# eeZeePowerJack.net
KiCad netlist of a schematic drawn in EAGLE
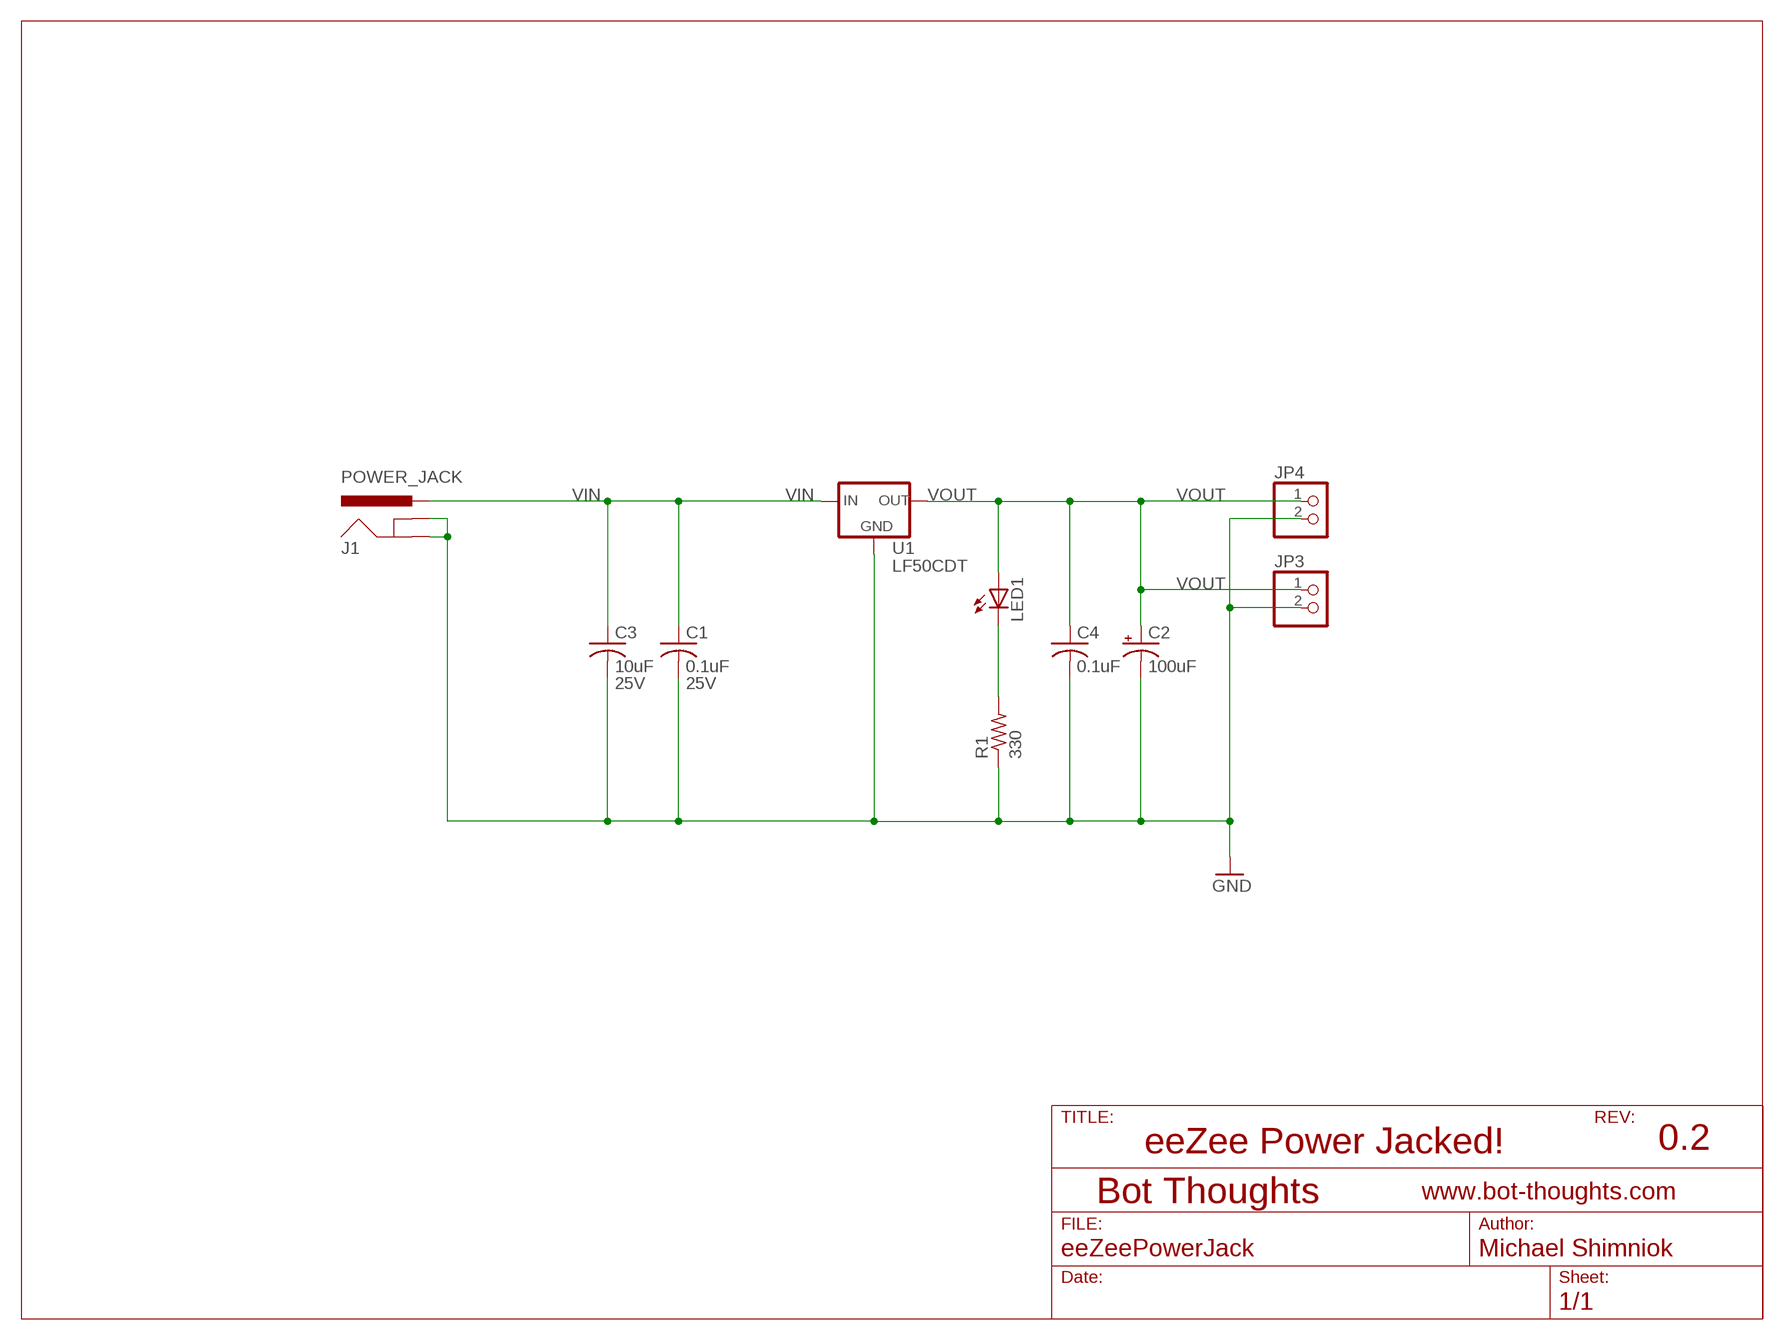
[diagram p0: schematic, sheet 1]

(export (version "E")
  (design (tool "Eeschema 10.0.6"))
  (components
    (comp (ref "C1")
      (value "0.1uF")
      (footprint "eagle-import:C0603")
      (fields (field (name "VOLTAGE") "25V"))
      (libsource (lib "eagle-import") (part "C-USC0603"))
    )
    (comp (ref "C2")
      (value "100uF")
      (footprint "eagle-import:SMC_B")
      (libsource (lib "eagle-import") (part "CPOL-USSMCB"))
    )
    (comp (ref "C3")
      (value "10uF")
      (footprint "eagle-import:C1206")
      (fields (field (name "VOLTAGE") "25V"))
      (libsource (lib "eagle-import") (part "C-USC1206"))
    )
    (comp (ref "C4")
      (value "0.1uF")
      (footprint "eagle-import:C0603")
      (libsource (lib "eagle-import") (part "C-USC0603"))
    )
    (comp (ref "J1")
      (value "POWER_JACK")
      (footprint "eagle-import:POWER_JACK_PTH")
      (libsource (lib "eagle-import") (part "POWER_JACKPTH"))
    )
    (comp (ref "JP3")
      (value "PINHD-1X02_2.54-S")
      (footprint "eagle-import:1X02-S")
      (libsource (lib "eagle-import") (part "PINHD-1X02_2.54-S"))
    )
    (comp (ref "JP4")
      (value "PINHD-1X02_2.54-S")
      (footprint "eagle-import:1X02-S")
      (libsource (lib "eagle-import") (part "PINHD-1X02_2.54-S"))
    )
    (comp (ref "LED1")
      (value "LEDCHIPLED_1206")
      (footprint "eagle-import:CHIPLED_1206")
      (libsource (lib "eagle-import") (part "LEDCHIPLED_1206"))
    )
    (comp (ref "R1")
      (value "330")
      (footprint "eagle-import:R0603")
      (libsource (lib "eagle-import") (part "R-US_R0603"))
    )
    (comp (ref "U1")
      (value "LF50CDT")
      (footprint "eagle-import:DPAK")
      (libsource (lib "eagle-import") (part "LF50CDT"))
    )
  )
  (nets
    (net (code "1") (name "/VIN") (class "Default")
      (node (ref "C1") (pin "1") (pinfunction "1_1") (pintype "passive"))
      (node (ref "C3") (pin "1") (pinfunction "1_1") (pintype "passive"))
      (node (ref "J1") (pin "PWR") (pinfunction "PWR_PWR") (pintype "bidirectional"))
      (node (ref "U1") (pin "1") (pinfunction "VIN_1") (pintype "bidirectional"))
    )
    (net (code "2") (name "/VOUT") (class "Default")
      (node (ref "C2") (pin "+") (pinfunction "+_+") (pintype "passive"))
      (node (ref "C4") (pin "1") (pinfunction "1_1") (pintype "passive"))
      (node (ref "JP3") (pin "1") (pinfunction "1_1") (pintype "passive"))
      (node (ref "JP4") (pin "1") (pinfunction "1_1") (pintype "passive"))
      (node (ref "LED1") (pin "A") (pinfunction "A_A") (pintype "passive"))
      (node (ref "U1") (pin "3") (pinfunction "VOUT_3") (pintype "bidirectional"))
    )
    (net (code "3") (name "GND") (class "Default")
      (node (ref "C1") (pin "2") (pinfunction "2_2") (pintype "passive"))
      (node (ref "C2") (pin "-") (pinfunction "-_-") (pintype "passive"))
      (node (ref "C3") (pin "2") (pinfunction "2_2") (pintype "passive"))
      (node (ref "C4") (pin "2") (pinfunction "2_2") (pintype "passive"))
      (node (ref "J1") (pin "GND") (pinfunction "GND_GND") (pintype "bidirectional"))
      (node (ref "J1") (pin "GNDBREAK") (pinfunction "GNDBREAK_GNDBREAK") (pintype "bidirectional"))
      (node (ref "JP3") (pin "2") (pinfunction "2_2") (pintype "passive"))
      (node (ref "JP4") (pin "2") (pinfunction "2_2") (pintype "passive"))
      (node (ref "R1") (pin "1") (pinfunction "1_1") (pintype "passive"))
      (node (ref "U1") (pin "4") (pinfunction "GND_4") (pintype "bidirectional"))
    )
    (net (code "4") (name "Net-(LED1-PadC)") (class "Default")
      (node (ref "LED1") (pin "C") (pinfunction "C_C") (pintype "passive"))
      (node (ref "R1") (pin "2") (pinfunction "2_2") (pintype "passive"))
    )
  )
)
